# U2S_ISP_JTAG.net
KiCad netlist of a schematic drawn in Altium Designer
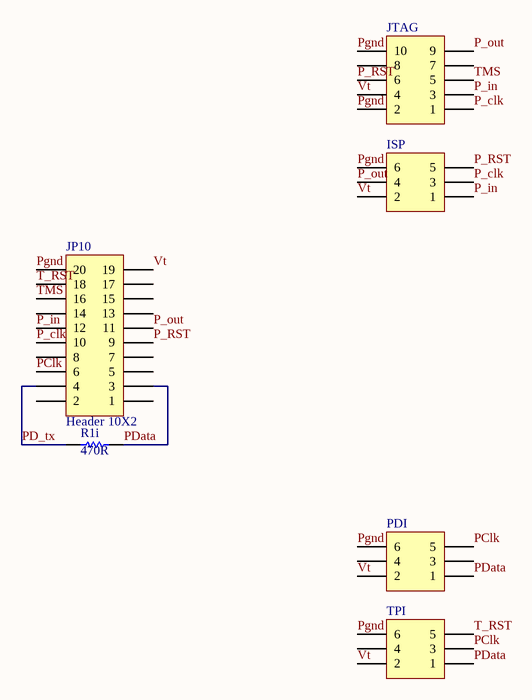
[diagram p0: U2S_ISP_JTAG.SchDoc]

(export (version "E")
  (design (tool "Eeschema 10.0.6"))
  (components
    (comp (ref "ISP")
      (value "Header 3X2")
      (footprint "HDR2X3")
      (description "Header, 3-Pin, Dual row")
      (fields (field (name "PUBLISHER") "Altium Limited"))
      (libsource (lib "Miscellaneous Connectors") (part "Header 3X2"))
    )
    (comp (ref "JP10")
      (value "Header 10X2")
      (footprint "HDR2X10")
      (description "Header, 10-Pin, Dual row")
      (fields (field (name "PUBLISHER") "Altium Limited"))
      (libsource (lib "Miscellaneous Connectors") (part "Header 10X2"))
    )
    (comp (ref "JTAG")
      (value "Header 5X2")
      (footprint "HDR2X5")
      (description "Header, 5-Pin, Dual row")
      (fields (field (name "PUBLISHER") "Altium Limited"))
      (libsource (lib "Miscellaneous Connectors") (part "Header 5X2"))
    )
    (comp (ref "PDI")
      (value "Header 3X2")
      (footprint "HDR2X3")
      (description "Header, 3-Pin, Dual row")
      (fields (field (name "PUBLISHER") "Altium Limited"))
      (libsource (lib "Miscellaneous Connectors") (part "Header 3X2"))
    )
    (comp (ref "R1i")
      (value "470R")
      (footprint "SMD0805")
      (fields (field (name "Comment") "Resistor"))
      (libsource (lib "MiscComponents") (part "Resistor"))
    )
    (comp (ref "TPI")
      (value "Header 3X2")
      (footprint "HDR2X3")
      (description "Header, 3-Pin, Dual row")
      (fields (field (name "PUBLISHER") "Altium Limited"))
      (libsource (lib "Miscellaneous Connectors") (part "Header 3X2"))
    )
  )
  (nets
    (net (code "1") (name "/PClk") (class "Default")
      (node (ref "JP10") (pin "6") (pinfunction "6_6") (pintype "passive"))
      (node (ref "PDI") (pin "5") (pinfunction "5_5") (pintype "passive"))
      (node (ref "TPI") (pin "3") (pinfunction "3_3") (pintype "passive"))
    )
    (net (code "2") (name "/PD_tx") (class "Default")
      (node (ref "JP10") (pin "4") (pinfunction "4_4") (pintype "passive"))
      (node (ref "R1i") (pin "1") (pinfunction "1_1") (pintype "passive"))
    )
    (net (code "3") (name "/PData") (class "Default")
      (node (ref "JP10") (pin "3") (pinfunction "3_3") (pintype "passive"))
      (node (ref "PDI") (pin "1") (pinfunction "1_1") (pintype "passive"))
      (node (ref "R1i") (pin "2") (pinfunction "2_2") (pintype "passive"))
      (node (ref "TPI") (pin "1") (pinfunction "1_1") (pintype "passive"))
    )
    (net (code "4") (name "/P_RST") (class "Default")
      (node (ref "ISP") (pin "5") (pinfunction "5_5") (pintype "passive"))
      (node (ref "JP10") (pin "9") (pinfunction "9_9") (pintype "passive"))
      (node (ref "JTAG") (pin "6") (pinfunction "6_6") (pintype "passive"))
    )
    (net (code "5") (name "/P_clk") (class "Default")
      (node (ref "ISP") (pin "3") (pinfunction "3_3") (pintype "passive"))
      (node (ref "JP10") (pin "10") (pinfunction "10_10") (pintype "passive"))
      (node (ref "JTAG") (pin "1") (pinfunction "1_1") (pintype "passive"))
    )
    (net (code "6") (name "/P_in") (class "Default")
      (node (ref "ISP") (pin "1") (pinfunction "1_1") (pintype "passive"))
      (node (ref "JP10") (pin "12") (pinfunction "12_12") (pintype "passive"))
      (node (ref "JTAG") (pin "3") (pinfunction "3_3") (pintype "passive"))
    )
    (net (code "7") (name "/P_out") (class "Default")
      (node (ref "ISP") (pin "4") (pinfunction "4_4") (pintype "passive"))
      (node (ref "JP10") (pin "11") (pinfunction "11_11") (pintype "passive"))
      (node (ref "JTAG") (pin "9") (pinfunction "9_9") (pintype "passive"))
    )
    (net (code "8") (name "/Pgnd") (class "Default")
      (node (ref "ISP") (pin "6") (pinfunction "6_6") (pintype "passive"))
      (node (ref "JP10") (pin "20") (pinfunction "20_20") (pintype "passive"))
      (node (ref "JTAG") (pin "10") (pinfunction "10_10") (pintype "passive"))
      (node (ref "JTAG") (pin "2") (pinfunction "2_2") (pintype "passive"))
      (node (ref "PDI") (pin "6") (pinfunction "6_6") (pintype "passive"))
      (node (ref "TPI") (pin "6") (pinfunction "6_6") (pintype "passive"))
    )
    (net (code "9") (name "/TMS") (class "Default")
      (node (ref "JP10") (pin "16") (pinfunction "16_16") (pintype "passive"))
      (node (ref "JTAG") (pin "5") (pinfunction "5_5") (pintype "passive"))
    )
    (net (code "10") (name "/T_RST") (class "Default")
      (node (ref "JP10") (pin "18") (pinfunction "18_18") (pintype "passive"))
      (node (ref "TPI") (pin "5") (pinfunction "5_5") (pintype "passive"))
    )
    (net (code "11") (name "/Vt") (class "Default")
      (node (ref "ISP") (pin "2") (pinfunction "2_2") (pintype "passive"))
      (node (ref "JP10") (pin "19") (pinfunction "19_19") (pintype "passive"))
      (node (ref "JTAG") (pin "4") (pinfunction "4_4") (pintype "passive"))
      (node (ref "PDI") (pin "2") (pinfunction "2_2") (pintype "passive"))
      (node (ref "TPI") (pin "2") (pinfunction "2_2") (pintype "passive"))
    )
    (net (code "12") (name "unconnected-(JP10-Pad1)") (class "Default")
      (node (ref "JP10") (pin "1") (pinfunction "1_1") (pintype "passive"))
    )
    (net (code "13") (name "unconnected-(JP10-Pad2)") (class "Default")
      (node (ref "JP10") (pin "2") (pinfunction "2_2") (pintype "passive"))
    )
    (net (code "14") (name "unconnected-(JP10-Pad5)") (class "Default")
      (node (ref "JP10") (pin "5") (pinfunction "5_5") (pintype "passive"))
    )
    (net (code "15") (name "unconnected-(JP10-Pad7)") (class "Default")
      (node (ref "JP10") (pin "7") (pinfunction "7_7") (pintype "passive"))
    )
    (net (code "16") (name "unconnected-(JP10-Pad8)") (class "Default")
      (node (ref "JP10") (pin "8") (pinfunction "8_8") (pintype "passive"))
    )
    (net (code "17") (name "unconnected-(JP10-Pad13)") (class "Default")
      (node (ref "JP10") (pin "13") (pinfunction "13_13") (pintype "passive"))
    )
    (net (code "18") (name "unconnected-(JP10-Pad14)") (class "Default")
      (node (ref "JP10") (pin "14") (pinfunction "14_14") (pintype "passive"))
    )
    (net (code "19") (name "unconnected-(JP10-Pad15)") (class "Default")
      (node (ref "JP10") (pin "15") (pinfunction "15_15") (pintype "passive"))
    )
    (net (code "20") (name "unconnected-(JP10-Pad17)") (class "Default")
      (node (ref "JP10") (pin "17") (pinfunction "17_17") (pintype "passive"))
    )
    (net (code "21") (name "unconnected-(JTAG-Pad7)") (class "Default")
      (node (ref "JTAG") (pin "7") (pinfunction "7_7") (pintype "passive"))
    )
    (net (code "22") (name "unconnected-(JTAG-Pad8)") (class "Default")
      (node (ref "JTAG") (pin "8") (pinfunction "8_8") (pintype "passive"))
    )
    (net (code "23") (name "unconnected-(PDI-Pad3)") (class "Default")
      (node (ref "PDI") (pin "3") (pinfunction "3_3") (pintype "passive"))
    )
    (net (code "24") (name "unconnected-(PDI-Pad4)") (class "Default")
      (node (ref "PDI") (pin "4") (pinfunction "4_4") (pintype "passive"))
    )
    (net (code "25") (name "unconnected-(TPI-Pad4)") (class "Default")
      (node (ref "TPI") (pin "4") (pinfunction "4_4") (pintype "passive"))
    )
  )
)
